# TC2030-MCP-NL-Adapter.net
KiCad netlist of a schematic drawn in EAGLE
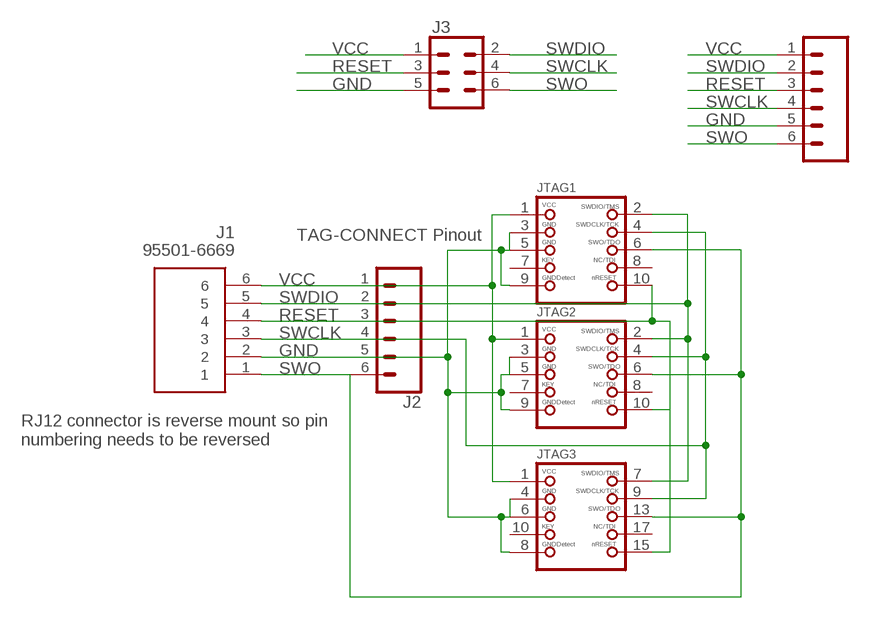
[diagram p0: schematic, sheet 1]

(export (version "E")
  (design (tool "Eeschema 10.0.6"))
  (components
    (comp (ref "J1")
      (value "95501-6669")
      (footprint "eagle-import:95501-6669")
      (fields (field (name "MOUSER_PART_NUMBER") "538-95501-6669"))
      (libsource (lib "eagle-import") (part "95501-6669"))
    )
    (comp (ref "J2")
      (value "CONN_06SILK_FEMALE_PTH")
      (footprint "eagle-import:1X06")
      (libsource (lib "eagle-import") (part "CONN_06SILK_FEMALE_PTH"))
    )
    (comp (ref "J3")
      (value "CONN_03X2NO_SILK")
      (footprint "eagle-import:2X3-NS")
      (libsource (lib "eagle-import") (part "CONN_03X2NO_SILK"))
    )
    (comp (ref "J6")
      (value "CONN_06SILK_FEMALE_PTH")
      (footprint "eagle-import:1X06")
      (libsource (lib "eagle-import") (part "CONN_06SILK_FEMALE_PTH"))
    )
    (comp (ref "JTAG1")
      (value "JTAG-CORTEXM3")
      (footprint "eagle-import:2X05_1.27MM_SMT")
      (libsource (lib "eagle-import") (part "JTAG-CORTEXM3"))
    )
    (comp (ref "JTAG2")
      (value "JTAG-CORTEXM3MOLEX")
      (footprint "eagle-import:CORTEXM3_SWD10_MOLEX")
      (libsource (lib "eagle-import") (part "JTAG-CORTEXM3MOLEX"))
    )
    (comp (ref "JTAG3")
      (value "JTAG-CORTEXM3MOLEX20")
      (footprint "eagle-import:JTAG-ARM")
      (libsource (lib "eagle-import") (part "JTAG-CORTEXM3MOLEX20"))
    )
  )
  (nets
    (net (code "1") (name "/GND") (class "Default")
      (node (ref "J1") (pin "2") (pinfunction "2_2") (pintype "bidirectional"))
      (node (ref "J2") (pin "5") (pinfunction "5_5") (pintype "passive"))
      (node (ref "J3") (pin "5") (pinfunction "5_5") (pintype "bidirectional"))
      (node (ref "J6") (pin "5") (pinfunction "5_5") (pintype "passive"))
      (node (ref "JTAG1") (pin "3") (pinfunction "3_3") (pintype "passive"))
      (node (ref "JTAG1") (pin "5") (pinfunction "5_5") (pintype "passive"))
      (node (ref "JTAG1") (pin "9") (pinfunction "9_9") (pintype "passive"))
      (node (ref "JTAG2") (pin "3") (pinfunction "3_3") (pintype "passive"))
      (node (ref "JTAG2") (pin "5") (pinfunction "5_5") (pintype "passive"))
      (node (ref "JTAG2") (pin "9") (pinfunction "9_9") (pintype "passive"))
      (node (ref "JTAG3") (pin "4") (pinfunction "3_4") (pintype "passive"))
      (node (ref "JTAG3") (pin "6") (pinfunction "5_6") (pintype "passive"))
      (node (ref "JTAG3") (pin "8") (pinfunction "9_8") (pintype "passive"))
    )
    (net (code "2") (name "/RESET") (class "Default")
      (node (ref "J1") (pin "4") (pinfunction "4_4") (pintype "bidirectional"))
      (node (ref "J2") (pin "3") (pinfunction "3_3") (pintype "passive"))
      (node (ref "J3") (pin "3") (pinfunction "3_3") (pintype "bidirectional"))
      (node (ref "J6") (pin "3") (pinfunction "3_3") (pintype "passive"))
      (node (ref "JTAG1") (pin "10") (pinfunction "10_10") (pintype "passive"))
      (node (ref "JTAG2") (pin "10") (pinfunction "10_10") (pintype "passive"))
      (node (ref "JTAG3") (pin "15") (pinfunction "10_15") (pintype "passive"))
    )
    (net (code "3") (name "/SWCLK") (class "Default")
      (node (ref "J1") (pin "3") (pinfunction "3_3") (pintype "bidirectional"))
      (node (ref "J2") (pin "4") (pinfunction "4_4") (pintype "passive"))
      (node (ref "J3") (pin "4") (pinfunction "4_4") (pintype "bidirectional"))
      (node (ref "J6") (pin "4") (pinfunction "4_4") (pintype "passive"))
      (node (ref "JTAG1") (pin "4") (pinfunction "4_4") (pintype "passive"))
      (node (ref "JTAG2") (pin "4") (pinfunction "4_4") (pintype "passive"))
      (node (ref "JTAG3") (pin "9") (pinfunction "4_9") (pintype "passive"))
    )
    (net (code "4") (name "/SWDIO") (class "Default")
      (node (ref "J1") (pin "5") (pinfunction "5_5") (pintype "bidirectional"))
      (node (ref "J2") (pin "2") (pinfunction "2_2") (pintype "passive"))
      (node (ref "J3") (pin "2") (pinfunction "2_2") (pintype "bidirectional"))
      (node (ref "J6") (pin "2") (pinfunction "2_2") (pintype "passive"))
      (node (ref "JTAG1") (pin "2") (pinfunction "2_2") (pintype "passive"))
      (node (ref "JTAG2") (pin "2") (pinfunction "2_2") (pintype "passive"))
      (node (ref "JTAG3") (pin "7") (pinfunction "2_7") (pintype "passive"))
    )
    (net (code "5") (name "/SWO") (class "Default")
      (node (ref "J1") (pin "1") (pinfunction "1_1") (pintype "bidirectional"))
      (node (ref "J2") (pin "6") (pinfunction "6_6") (pintype "passive"))
      (node (ref "J3") (pin "6") (pinfunction "6_6") (pintype "bidirectional"))
      (node (ref "J6") (pin "6") (pinfunction "6_6") (pintype "passive"))
      (node (ref "JTAG1") (pin "6") (pinfunction "6_6") (pintype "passive"))
      (node (ref "JTAG2") (pin "6") (pinfunction "6_6") (pintype "passive"))
      (node (ref "JTAG3") (pin "13") (pinfunction "6_13") (pintype "passive"))
    )
    (net (code "6") (name "/VCC") (class "Default")
      (node (ref "J1") (pin "6") (pinfunction "6_6") (pintype "bidirectional"))
      (node (ref "J2") (pin "1") (pinfunction "1_1") (pintype "passive"))
      (node (ref "J3") (pin "1") (pinfunction "1_1") (pintype "bidirectional"))
      (node (ref "J6") (pin "1") (pinfunction "1_1") (pintype "passive"))
      (node (ref "JTAG1") (pin "1") (pinfunction "1_1") (pintype "passive"))
      (node (ref "JTAG2") (pin "1") (pinfunction "1_1") (pintype "passive"))
      (node (ref "JTAG3") (pin "1") (pinfunction "1_1") (pintype "passive"))
    )
    (net (code "7") (name "unconnected-(JTAG1-Pad7)") (class "Default")
      (node (ref "JTAG1") (pin "7") (pinfunction "7_7") (pintype "passive"))
    )
    (net (code "8") (name "unconnected-(JTAG1-Pad8)") (class "Default")
      (node (ref "JTAG1") (pin "8") (pinfunction "8_8") (pintype "passive"))
    )
    (net (code "9") (name "unconnected-(JTAG2-Pad7)") (class "Default")
      (node (ref "JTAG2") (pin "7") (pinfunction "7_7") (pintype "passive"))
    )
    (net (code "10") (name "unconnected-(JTAG2-Pad8)") (class "Default")
      (node (ref "JTAG2") (pin "8") (pinfunction "8_8") (pintype "passive"))
    )
    (net (code "11") (name "unconnected-(JTAG3-7-Pad10)") (class "Default")
      (node (ref "JTAG3") (pin "10") (pinfunction "7_10") (pintype "passive"))
    )
    (net (code "12") (name "unconnected-(JTAG3-8-Pad17)") (class "Default")
      (node (ref "JTAG3") (pin "17") (pinfunction "8_17") (pintype "passive"))
    )
  )
)
